# serial.net
KiCad netlist of a schematic drawn in Altium Designer
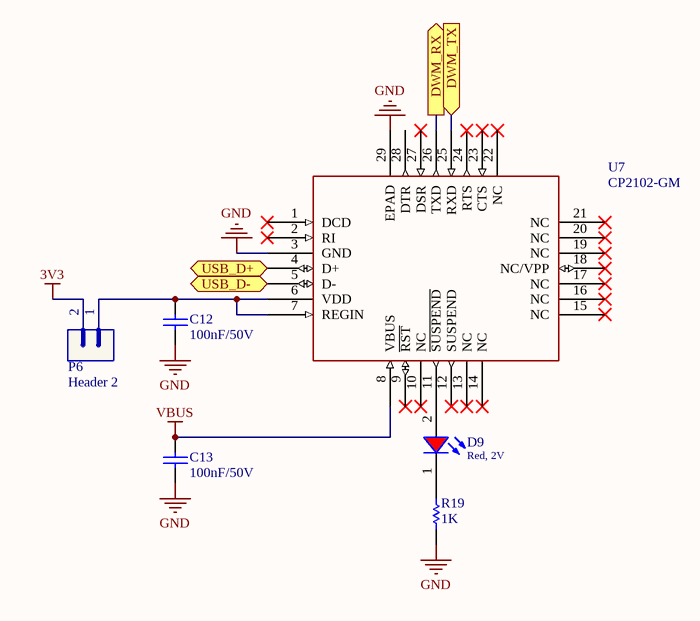
[diagram p0: serial.SchDoc]

(export (version "E")
  (design (tool "Eeschema 10.0.6"))
  (components
    (comp (ref "C12")
      (value "100nF/50V")
      (footprint "CAP-SM-0805")
      (description "CAP CER 0.1UF 50V Y5V 0805")
      (fields
        (field (name "MANUFACTURER") "Samsung Electro-Mechanics")
        (field (name "MANUFACTURER PART NUMBER") "CL21F104ZBCNNNC")
      )
      (libsource (lib "Capacitor") (part "Cap-100nF-50V-0805"))
    )
    (comp (ref "C13")
      (value "100nF/50V")
      (footprint "CAP-SM-0805")
      (description "CAP CER 0.1UF 50V Y5V 0805")
      (fields
        (field (name "MANUFACTURER") "Samsung Electro-Mechanics")
        (field (name "MANUFACTURER PART NUMBER") "CL21F104ZBCNNNC")
      )
      (libsource (lib "Capacitor") (part "Cap-100nF-50V-0805"))
    )
    (comp (ref "D9")
      (value "Red, 2V")
      (footprint "WL-SMCW_0805")
      (description "WL-SMCW SMT Mono-color Chip LED Waterclear, size 0805, Red, 2V, 140deg")
      (fields (field (name "PART NUMBER") "150080RS75000") (field (name "PUBLISHER") "Wurth Elektronik"))
      (libsource (lib "led-smd-0805") (part "150080RS75000"))
    )
    (comp (ref "P6")
      (value "Header 2")
      (footprint "JP2")
      (description "Header, 2-Pin")
      (fields (field (name "LOCAL SUPPLIER PART NUMBER") "x") (field (name "PUBLISHER") "Altium Limited"))
      (libsource (lib "header-connector") (part "Header 2"))
    )
    (comp (ref "R19")
      (value "1K")
      (footprint "resistor-smd:RES-SM-0805")
      (description "RES 1K OHM 1% 1/4W 0805")
      (fields
        (field (name "MANUFACTURER") "Stackpole Electronics Inc")
        (field (name "MANUFACTURER PART NUMBER") "RNCP0805FTD1K00")
      )
      (libsource (lib "resistor-smd") (part "Res-1K-0805"))
    )
    (comp (ref "U7")
      (value "CP2102-GM")
      (footprint "QFN28_5X5_SIL")
      (fields (field (name "COPYRIGHT") "Copyright (C) 2018 Accelerated Designs. All rights reserved"))
      (libsource (lib "functional-ic") (part "CP2102-GM"))
    )
  )
  (nets
    (net (code "1") (name "/DWM_RX") (class "Default")
      (node (ref "U7") (pin "26") (pinfunction "TXD_26") (pintype "output"))
    )
    (net (code "2") (name "/DWM_TX") (class "Default")
      (node (ref "U7") (pin "25") (pinfunction "RXD_25") (pintype "input"))
    )
    (net (code "3") (name "/USB_D+") (class "Default")
      (node (ref "U7") (pin "4") (pinfunction "D+_4") (pintype "bidirectional"))
    )
    (net (code "4") (name "/USB_D-") (class "Default")
      (node (ref "U7") (pin "5") (pinfunction "D-_5") (pintype "bidirectional"))
    )
    (net (code "5") (name "3V3") (class "Default")
      (node (ref "P6") (pin "2") (pinfunction "2_2") (pintype "passive"))
    )
    (net (code "6") (name "GND") (class "Default")
      (node (ref "C12") (pin "1") (pinfunction "1_1") (pintype "passive"))
      (node (ref "C13") (pin "1") (pinfunction "1_1") (pintype "passive"))
      (node (ref "R19") (pin "1") (pinfunction "1_1") (pintype "passive"))
      (node (ref "U7") (pin "29") (pinfunction "EPAD_29") (pintype "passive"))
      (node (ref "U7") (pin "3") (pinfunction "GND_3") (pintype "power_in"))
    )
    (net (code "7") (name "Net-(D9-A)") (class "Default")
      (node (ref "D9") (pin "2") (pinfunction "A_2") (pintype "passive"))
      (node (ref "U7") (pin "11") (pinfunction "~{SUSPEND}_11") (pintype "output"))
    )
    (net (code "8") (name "Net-(D9-K)") (class "Default")
      (node (ref "D9") (pin "1") (pinfunction "K_1") (pintype "passive"))
      (node (ref "R19") (pin "2") (pinfunction "2_2") (pintype "passive"))
    )
    (net (code "9") (name "Net-(U7-REGIN)") (class "Default")
      (node (ref "C12") (pin "2") (pinfunction "2_2") (pintype "passive"))
      (node (ref "P6") (pin "1") (pinfunction "1_1") (pintype "passive"))
      (node (ref "U7") (pin "6") (pinfunction "VDD_6") (pintype "power_in"))
      (node (ref "U7") (pin "7") (pinfunction "REGIN_7") (pintype "input"))
    )
    (net (code "10") (name "VBUS") (class "Default")
      (node (ref "C13") (pin "2") (pinfunction "2_2") (pintype "passive"))
      (node (ref "U7") (pin "8") (pinfunction "VBUS_8") (pintype "input"))
    )
    (net (code "11") (name "unconnected-(U7-CTS-Pad23)") (class "Default")
      (node (ref "U7") (pin "23") (pinfunction "CTS_23") (pintype "input+no_connect"))
    )
    (net (code "12") (name "unconnected-(U7-DCD-Pad1)") (class "Default")
      (node (ref "U7") (pin "1") (pinfunction "DCD_1") (pintype "input+no_connect"))
    )
    (net (code "13") (name "unconnected-(U7-DSR-Pad27)") (class "Default")
      (node (ref "U7") (pin "27") (pinfunction "DSR_27") (pintype "input+no_connect"))
    )
    (net (code "14") (name "unconnected-(U7-DTR-Pad28)") (class "Default")
      (node (ref "U7") (pin "28") (pinfunction "DTR_28") (pintype "output"))
    )
    (net (code "15") (name "unconnected-(U7-NC-Pad10)") (class "Default")
      (node (ref "U7") (pin "10") (pinfunction "NC_10") (pintype "passive+no_connect"))
    )
    (net (code "16") (name "unconnected-(U7-NC-Pad13)") (class "Default")
      (node (ref "U7") (pin "13") (pinfunction "NC_13") (pintype "passive+no_connect"))
    )
    (net (code "17") (name "unconnected-(U7-NC-Pad14)") (class "Default")
      (node (ref "U7") (pin "14") (pinfunction "NC_14") (pintype "passive+no_connect"))
    )
    (net (code "18") (name "unconnected-(U7-NC-Pad15)") (class "Default")
      (node (ref "U7") (pin "15") (pinfunction "NC_15") (pintype "passive+no_connect"))
    )
    (net (code "19") (name "unconnected-(U7-NC-Pad16)") (class "Default")
      (node (ref "U7") (pin "16") (pinfunction "NC_16") (pintype "passive+no_connect"))
    )
    (net (code "20") (name "unconnected-(U7-NC-Pad17)") (class "Default")
      (node (ref "U7") (pin "17") (pinfunction "NC_17") (pintype "passive+no_connect"))
    )
    (net (code "21") (name "unconnected-(U7-NC-Pad19)") (class "Default")
      (node (ref "U7") (pin "19") (pinfunction "NC_19") (pintype "passive+no_connect"))
    )
    (net (code "22") (name "unconnected-(U7-NC-Pad20)") (class "Default")
      (node (ref "U7") (pin "20") (pinfunction "NC_20") (pintype "passive+no_connect"))
    )
    (net (code "23") (name "unconnected-(U7-NC-Pad21)") (class "Default")
      (node (ref "U7") (pin "21") (pinfunction "NC_21") (pintype "passive+no_connect"))
    )
    (net (code "24") (name "unconnected-(U7-NC-Pad22)") (class "Default")
      (node (ref "U7") (pin "22") (pinfunction "NC_22") (pintype "passive+no_connect"))
    )
    (net (code "25") (name "unconnected-(U7-NC{slash}VPP-Pad18)") (class "Default")
      (node (ref "U7") (pin "18") (pinfunction "NC/VPP_18") (pintype "bidirectional+no_connect"))
    )
    (net (code "26") (name "unconnected-(U7-RI-Pad2)") (class "Default")
      (node (ref "U7") (pin "2") (pinfunction "RI_2") (pintype "input+no_connect"))
    )
    (net (code "27") (name "unconnected-(U7-RTS-Pad24)") (class "Default")
      (node (ref "U7") (pin "24") (pinfunction "RTS_24") (pintype "output+no_connect"))
    )
    (net (code "28") (name "unconnected-(U7-SUSPEND-Pad12)") (class "Default")
      (node (ref "U7") (pin "12") (pinfunction "SUSPEND_12") (pintype "output+no_connect"))
    )
    (net (code "29") (name "unconnected-(U7-~{RST}-Pad9)") (class "Default")
      (node (ref "U7") (pin "9") (pinfunction "~{RST}_9") (pintype "bidirectional+no_connect"))
    )
  )
)
